# BH1750.net
KiCad netlist of a schematic drawn in Altium Designer
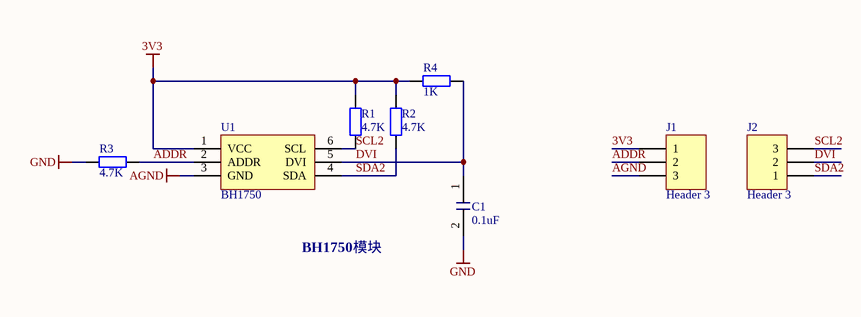
[diagram p0: BH1750原理图.SchDoc]

(export (version "E")
  (design (tool "Eeschema 10.0.6"))
  (components
    (comp (ref "C1")
      (value "无极性贴片电容")
      (footprint "C 0603_M")
      (fields (field (name "ALTIUM_UNNAMED_1") "0.1uF"))
      (libsource (lib "CCC") (part "贴片电容"))
    )
    (comp (ref "J1")
      (value "Header 3")
      (footprint "HDR1X3")
      (description "Header, 3-Pin")
      (fields (field (name "PUBLISHER") "Altium Limited"))
      (libsource (lib "Miscellaneous Connectors") (part "Header 3"))
    )
    (comp (ref "J2")
      (value "Header 3")
      (footprint "HDR1X3")
      (description "Header, 3-Pin")
      (fields (field (name "PUBLISHER") "Altium Limited"))
      (libsource (lib "") (part "Header 3_1"))
    )
    (comp (ref "R1")
      (value "4.7K")
      (footprint "R 0603_L")
      (description "Resistor")
      (fields (field (name "Comment") "Res2") (field (name "PUBLISHER") "Altium Limited"))
      (libsource (lib "") (part "Res2_1"))
    )
    (comp (ref "R2")
      (value "4.7K")
      (footprint "R 0603_L")
      (description "Resistor")
      (fields (field (name "Comment") "Res2") (field (name "PUBLISHER") "Altium Limited"))
      (libsource (lib "") (part "Res2_1"))
    )
    (comp (ref "R3")
      (value "4.7K")
      (footprint "R 0603_L")
      (description "Resistor")
      (fields (field (name "Comment") "Res2") (field (name "PUBLISHER") "Altium Limited"))
      (libsource (lib "Miscellaneous Devices") (part "Res2"))
    )
    (comp (ref "R4")
      (value "1K")
      (footprint "R 0603_L")
      (description "Resistor")
      (fields (field (name "Comment") "Res2") (field (name "PUBLISHER") "Altium Limited"))
      (libsource (lib "Miscellaneous Devices") (part "Res2"))
    )
    (comp (ref "U1") (value "BH1750") (footprint "BH1750FVI") (libsource (lib "BH1750") (part "BH1750")))
  )
  (nets
    (net (code "1") (name "/ADDR") (class "Default")
      (node (ref "J1") (pin "2") (pinfunction "2_2") (pintype "passive"))
      (node (ref "R3") (pin "1") (pinfunction "1_1") (pintype "passive"))
      (node (ref "U1") (pin "2") (pinfunction "ADDR_2") (pintype "passive"))
    )
    (net (code "2") (name "/DVI") (class "Default")
      (node (ref "C1") (pin "1") (pinfunction "0_1") (pintype "passive"))
      (node (ref "J2") (pin "2") (pinfunction "2_2") (pintype "passive"))
      (node (ref "R4") (pin "1") (pinfunction "1_1") (pintype "passive"))
      (node (ref "U1") (pin "5") (pinfunction "DVI_5") (pintype "passive"))
    )
    (net (code "3") (name "/SCL2") (class "Default")
      (node (ref "J2") (pin "3") (pinfunction "3_3") (pintype "passive"))
      (node (ref "R1") (pin "1") (pinfunction "1_1") (pintype "passive"))
      (node (ref "U1") (pin "6") (pinfunction "SCL_6") (pintype "passive"))
    )
    (net (code "4") (name "/SDA2") (class "Default")
      (node (ref "J2") (pin "1") (pinfunction "1_1") (pintype "passive"))
      (node (ref "R2") (pin "1") (pinfunction "1_1") (pintype "passive"))
      (node (ref "U1") (pin "4") (pinfunction "SDA_4") (pintype "passive"))
    )
    (net (code "5") (name "3V3") (class "Default")
      (node (ref "J1") (pin "1") (pinfunction "1_1") (pintype "passive"))
      (node (ref "R1") (pin "2") (pinfunction "2_2") (pintype "passive"))
      (node (ref "R2") (pin "2") (pinfunction "2_2") (pintype "passive"))
      (node (ref "R4") (pin "2") (pinfunction "2_2") (pintype "passive"))
      (node (ref "U1") (pin "1") (pinfunction "VCC_1") (pintype "passive"))
    )
    (net (code "6") (name "AGND") (class "Default")
      (node (ref "J1") (pin "3") (pinfunction "3_3") (pintype "passive"))
      (node (ref "U1") (pin "3") (pinfunction "GND_3") (pintype "passive"))
    )
    (net (code "7") (name "GND") (class "Default")
      (node (ref "C1") (pin "2") (pinfunction "1_2") (pintype "passive"))
      (node (ref "R3") (pin "2") (pinfunction "2_2") (pintype "passive"))
    )
  )
)
